# 117_02_TIMER_GATE.net
KiCad netlist of a schematic drawn in EAGLE
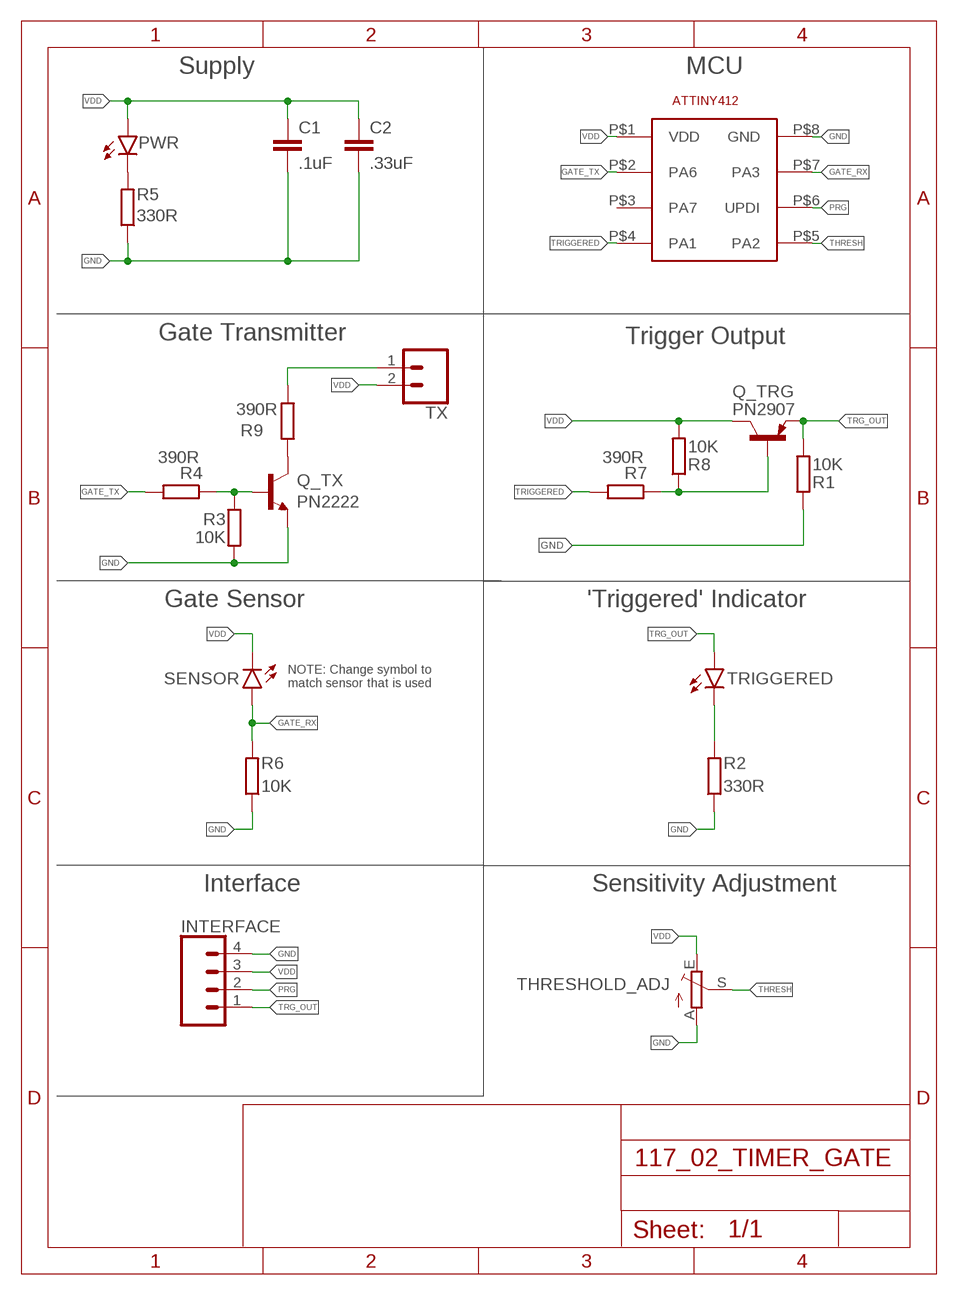
[diagram p0: schematic, sheet 1]

(export (version "E")
  (design (tool "Eeschema 10.0.6"))
  (components
    (comp (ref "C1")
      (value ".1uF")
      (footprint "eagle-import:C0805K")
      (libsource (lib "eagle-import") (part "C-EUC0805K"))
    )
    (comp (ref "C2")
      (value ".33uF")
      (footprint "eagle-import:C0805K")
      (libsource (lib "eagle-import") (part "C-EUC0805K"))
    )
    (comp (ref "INTERFACE")
      (value "CONN_04LONGPADS")
      (footprint "eagle-import:1X04_LONGPADS")
      (libsource (lib "eagle-import") (part "CONN_04LONGPADS"))
    )
    (comp (ref "PWR")
      (value "LEDSML0805")
      (footprint "eagle-import:SML0805")
      (libsource (lib "eagle-import") (part "LEDSML0805"))
    )
    (comp (ref "Q_TRG")
      (value "PN2907")
      (footprint "eagle-import:TO92-CBE")
      (libsource (lib "eagle-import") (part "-PNP-TO92-CBE2N4126"))
    )
    (comp (ref "Q_TX")
      (value "PN2222")
      (footprint "eagle-import:TO92-EBC")
      (libsource (lib "eagle-import") (part "-NPN-TO92-EBC2N2222"))
    )
    (comp (ref "R1")
      (value "10K")
      (footprint "eagle-import:M0805")
      (libsource (lib "eagle-import") (part "R-EU_M0805"))
    )
    (comp (ref "R2")
      (value "330R")
      (footprint "eagle-import:M0805")
      (libsource (lib "eagle-import") (part "R-EU_M0805"))
    )
    (comp (ref "R3")
      (value "10K")
      (footprint "eagle-import:M0805")
      (libsource (lib "eagle-import") (part "R-EU_M0805"))
    )
    (comp (ref "R4")
      (value "390R")
      (footprint "eagle-import:M0805")
      (libsource (lib "eagle-import") (part "R-EU_M0805"))
    )
    (comp (ref "R5")
      (value "330R")
      (footprint "eagle-import:M0805")
      (libsource (lib "eagle-import") (part "R-EU_M0805"))
    )
    (comp (ref "R6")
      (value "10K")
      (footprint "eagle-import:M0805")
      (libsource (lib "eagle-import") (part "R-EU_M0805"))
    )
    (comp (ref "R7")
      (value "390R")
      (footprint "eagle-import:M0805")
      (libsource (lib "eagle-import") (part "R-EU_M0805"))
    )
    (comp (ref "R8")
      (value "10K")
      (footprint "eagle-import:M0805")
      (libsource (lib "eagle-import") (part "R-EU_M0805"))
    )
    (comp (ref "R9")
      (value "390R")
      (footprint "eagle-import:M0805")
      (libsource (lib "eagle-import") (part "R-EU_M0805"))
    )
    (comp (ref "SENSOR")
      (value "LED5MM")
      (footprint "eagle-import:LED_5MM")
      (libsource (lib "eagle-import") (part "LED5MM"))
    )
    (comp (ref "THRESHOLD_ADJ")
      (value "TRIM_EU-S64W")
      (footprint "eagle-import:S64W")
      (libsource (lib "eagle-import") (part "TRIM_EU-S64W"))
    )
    (comp (ref "TRIGGERED")
      (value "LED5MM")
      (footprint "eagle-import:LED_5MM")
      (libsource (lib "eagle-import") (part "LED5MM"))
    )
    (comp (ref "TX")
      (value "CONN_02PTH3")
      (footprint "eagle-import:1X02_LONGPADS")
      (libsource (lib "eagle-import") (part "CONN_02PTH3"))
    )
    (comp (ref "U$1")
      (value "ATTINY412")
      (footprint "eagle-import:ATTINY412")
      (libsource (lib "eagle-import") (part "ATTINY412"))
    )
  )
  (nets
    (net (code "1") (name "GATE_RX") (class "Default")
      (node (ref "R6") (pin "2") (pinfunction "2_2") (pintype "passive"))
      (node (ref "SENSOR") (pin "A") (pinfunction "A_A") (pintype "passive"))
      (node (ref "U$1") (pin "P$7") (pinfunction "PA3_P$7") (pintype "bidirectional"))
    )
    (net (code "2") (name "GATE_TX") (class "Default")
      (node (ref "R4") (pin "2") (pinfunction "2_2") (pintype "passive"))
      (node (ref "U$1") (pin "P$2") (pinfunction "PA6_P$2") (pintype "bidirectional"))
    )
    (net (code "3") (name "GND") (class "Default")
      (node (ref "C1") (pin "2") (pinfunction "2_2") (pintype "passive"))
      (node (ref "C2") (pin "2") (pinfunction "2_2") (pintype "passive"))
      (node (ref "INTERFACE") (pin "4") (pinfunction "4_4") (pintype "passive"))
      (node (ref "Q_TX") (pin "E") (pinfunction "E_E") (pintype "passive"))
      (node (ref "R1") (pin "1") (pinfunction "1_1") (pintype "passive"))
      (node (ref "R2") (pin "1") (pinfunction "1_1") (pintype "passive"))
      (node (ref "R3") (pin "2") (pinfunction "2_2") (pintype "passive"))
      (node (ref "R5") (pin "1") (pinfunction "1_1") (pintype "passive"))
      (node (ref "R6") (pin "1") (pinfunction "1_1") (pintype "passive"))
      (node (ref "THRESHOLD_ADJ") (pin "A") (pinfunction "A_A") (pintype "passive"))
      (node (ref "U$1") (pin "P$8") (pinfunction "GND_P$8") (pintype "bidirectional"))
    )
    (net (code "4") (name "Net-(PWR-PadC)") (class "Default")
      (node (ref "PWR") (pin "C") (pinfunction "C_C") (pintype "passive"))
      (node (ref "R5") (pin "2") (pinfunction "2_2") (pintype "passive"))
    )
    (net (code "5") (name "Net-(Q_TRG-PadB)") (class "Default")
      (node (ref "Q_TRG") (pin "B") (pinfunction "B_B") (pintype "passive"))
      (node (ref "R7") (pin "1") (pinfunction "1_1") (pintype "passive"))
      (node (ref "R8") (pin "1") (pinfunction "1_1") (pintype "passive"))
    )
    (net (code "6") (name "Net-(Q_TX-PadB)") (class "Default")
      (node (ref "Q_TX") (pin "B") (pinfunction "B_B") (pintype "passive"))
      (node (ref "R3") (pin "1") (pinfunction "1_1") (pintype "passive"))
      (node (ref "R4") (pin "1") (pinfunction "1_1") (pintype "passive"))
    )
    (net (code "7") (name "Net-(Q_TX-PadC)") (class "Default")
      (node (ref "Q_TX") (pin "C") (pinfunction "C_C") (pintype "passive"))
      (node (ref "R9") (pin "2") (pinfunction "2_2") (pintype "passive"))
    )
    (net (code "8") (name "Net-(R9-Pad1)") (class "Default")
      (node (ref "R9") (pin "1") (pinfunction "1_1") (pintype "passive"))
      (node (ref "TX") (pin "1") (pinfunction "1_1") (pintype "passive"))
    )
    (net (code "9") (name "Net-(TRIGGERED-C)") (class "Default")
      (node (ref "R2") (pin "2") (pinfunction "2_2") (pintype "passive"))
      (node (ref "TRIGGERED") (pin "K") (pinfunction "C_K") (pintype "passive"))
    )
    (net (code "10") (name "PRG") (class "Default")
      (node (ref "INTERFACE") (pin "2") (pinfunction "2_2") (pintype "passive"))
      (node (ref "U$1") (pin "P$6") (pinfunction "UPDI_P$6") (pintype "bidirectional"))
    )
    (net (code "11") (name "THRESH") (class "Default")
      (node (ref "THRESHOLD_ADJ") (pin "S") (pinfunction "S_S") (pintype "passive"))
      (node (ref "U$1") (pin "P$5") (pinfunction "PA2_P$5") (pintype "bidirectional"))
    )
    (net (code "12") (name "TRG_OUT") (class "Default")
      (node (ref "INTERFACE") (pin "1") (pinfunction "1_1") (pintype "passive"))
      (node (ref "Q_TRG") (pin "E") (pinfunction "E_E") (pintype "passive"))
      (node (ref "R1") (pin "2") (pinfunction "2_2") (pintype "passive"))
      (node (ref "TRIGGERED") (pin "A") (pinfunction "A_A") (pintype "passive"))
    )
    (net (code "13") (name "TRIGGERED") (class "Default")
      (node (ref "R7") (pin "2") (pinfunction "2_2") (pintype "passive"))
      (node (ref "U$1") (pin "P$4") (pinfunction "PA1_P$4") (pintype "bidirectional"))
    )
    (net (code "14") (name "VDD") (class "Default")
      (node (ref "C1") (pin "1") (pinfunction "1_1") (pintype "passive"))
      (node (ref "C2") (pin "1") (pinfunction "1_1") (pintype "passive"))
      (node (ref "INTERFACE") (pin "3") (pinfunction "3_3") (pintype "passive"))
      (node (ref "PWR") (pin "A") (pinfunction "A_A") (pintype "passive"))
      (node (ref "Q_TRG") (pin "C") (pinfunction "C_C") (pintype "passive"))
      (node (ref "R8") (pin "2") (pinfunction "2_2") (pintype "passive"))
      (node (ref "SENSOR") (pin "K") (pinfunction "C_K") (pintype "passive"))
      (node (ref "THRESHOLD_ADJ") (pin "E") (pinfunction "E_E") (pintype "passive"))
      (node (ref "TX") (pin "2") (pinfunction "2_2") (pintype "passive"))
      (node (ref "U$1") (pin "P$1") (pinfunction "VDD_P$1") (pintype "bidirectional"))
    )
    (net (code "15") (name "unconnected-(U$1-PA7-PadP$3)") (class "Default")
      (node (ref "U$1") (pin "P$3") (pinfunction "PA7_P$3") (pintype "bidirectional"))
    )
  )
)
